# magnetorquer_board.net
KiCad netlist of a schematic drawn in EAGLE
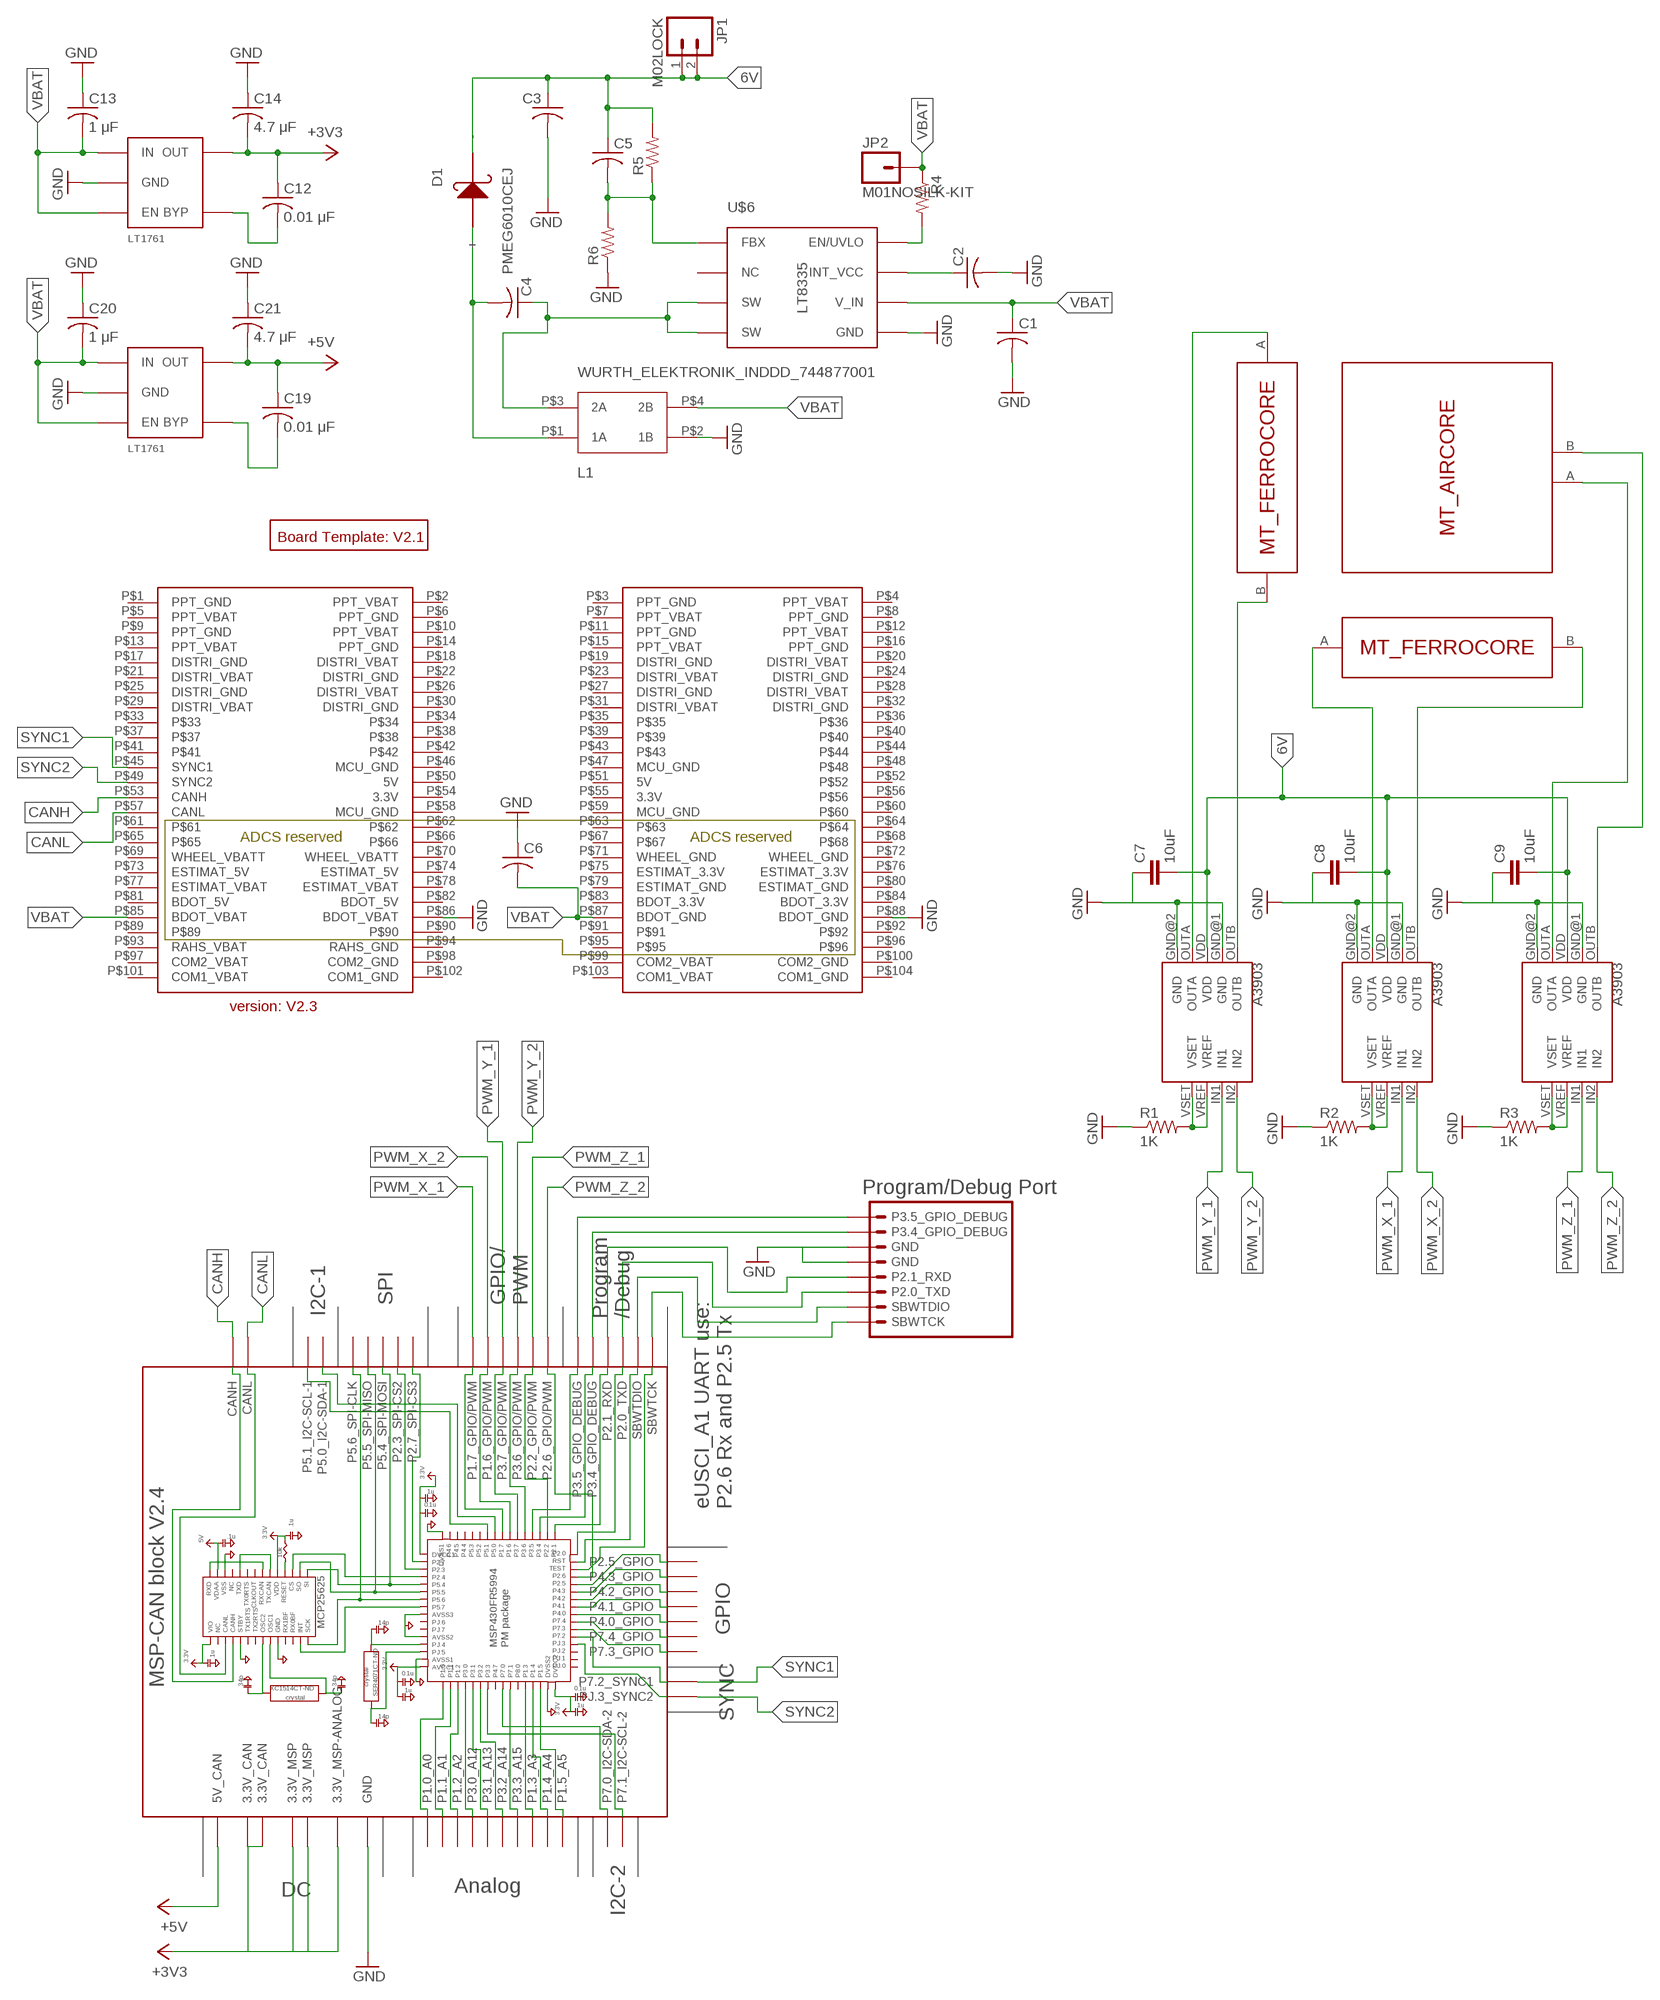
[diagram p0: schematic, sheet 1]

(export (version "E")
  (design (tool "Eeschema 10.0.6"))
  (components
    (comp (ref "C1")
      (value "C-USC0805")
      (footprint "eagle-import:C0805")
      (libsource (lib "eagle-import") (part "C-USC0805"))
    )
    (comp (ref "C2")
      (value "C-USC0805")
      (footprint "eagle-import:C0805")
      (libsource (lib "eagle-import") (part "C-USC0805"))
    )
    (comp (ref "C3")
      (value "C-USC0805")
      (footprint "eagle-import:C0805")
      (libsource (lib "eagle-import") (part "C-USC0805"))
    )
    (comp (ref "C4")
      (value "C-USC0805")
      (footprint "eagle-import:C0805")
      (libsource (lib "eagle-import") (part "C-USC0805"))
    )
    (comp (ref "C5")
      (value "C-USC0805")
      (footprint "eagle-import:C0805")
      (libsource (lib "eagle-import") (part "C-USC0805"))
    )
    (comp (ref "C6")
      (value "C-USC0805")
      (footprint "eagle-import:C0805")
      (libsource (lib "eagle-import") (part "C-USC0805"))
    )
    (comp (ref "C7")
      (value "10uF")
      (footprint "eagle-import:C0805")
      (libsource (lib "eagle-import") (part "C-EUC0805"))
    )
    (comp (ref "C8")
      (value "10uF")
      (footprint "eagle-import:C0805")
      (libsource (lib "eagle-import") (part "C-EUC0805"))
    )
    (comp (ref "C9")
      (value "10uF")
      (footprint "eagle-import:C0805")
      (libsource (lib "eagle-import") (part "C-EUC0805"))
    )
    (comp (ref "C12")
      (value "0.01 μF")
      (footprint "eagle-import:C0805")
      (libsource (lib "eagle-import") (part "C-USC0805"))
    )
    (comp (ref "C13")
      (value "1 μF")
      (footprint "eagle-import:C0805")
      (libsource (lib "eagle-import") (part "C-USC0805"))
    )
    (comp (ref "C14")
      (value "4.7 μF")
      (footprint "eagle-import:C0805")
      (libsource (lib "eagle-import") (part "C-USC0805"))
    )
    (comp (ref "C19")
      (value "0.01 μF")
      (footprint "eagle-import:C0805")
      (libsource (lib "eagle-import") (part "C-USC0805"))
    )
    (comp (ref "C20")
      (value "1 μF")
      (footprint "eagle-import:C0805")
      (libsource (lib "eagle-import") (part "C-USC0805"))
    )
    (comp (ref "C21")
      (value "4.7 μF")
      (footprint "eagle-import:C0805")
      (libsource (lib "eagle-import") (part "C-USC0805"))
    )
    (comp (ref "D1")
      (value "PMEG6010CEJ")
      (footprint "eagle-import:SC-90")
      (libsource (lib "eagle-import") (part "PMEG6010CEJ"))
    )
    (comp (ref "JP1")
      (value "M02LOCK")
      (footprint "eagle-import:1X02_LOCK")
      (libsource (lib "eagle-import") (part "M02LOCK"))
    )
    (comp (ref "JP2")
      (value "M01NOSILK-KIT")
      (footprint "eagle-import:1X01NS-KIT")
      (libsource (lib "eagle-import") (part "M01NOSILK-KIT"))
    )
    (comp (ref "L1")
      (value "WURTH_ELEKTRONIK_INDDD_744877001")
      (footprint "eagle-import:WURTH_ELEKTRONIK_INDDD_744877001")
      (libsource (lib "eagle-import") (part "WURTH_ELEKTRONIK_INDDD_744877001"))
    )
    (comp (ref "LDO_3V1")
      (value "LINEAR_LDO_LT1761-X")
      (footprint "eagle-import:SOT-23-5")
      (libsource (lib "eagle-import") (part "LINEAR_LDO_LT1761-X"))
    )
    (comp (ref "LDO_5V1")
      (value "LINEAR_LDO_LT1761-X")
      (footprint "eagle-import:SOT-23-5")
      (libsource (lib "eagle-import") (part "LINEAR_LDO_LT1761-X"))
    )
    (comp (ref "R1")
      (value "1K")
      (footprint "eagle-import:R0603")
      (libsource (lib "eagle-import") (part "R-US_R0603"))
    )
    (comp (ref "R2")
      (value "1K")
      (footprint "eagle-import:R0603")
      (libsource (lib "eagle-import") (part "R-US_R0603"))
    )
    (comp (ref "R3")
      (value "1K")
      (footprint "eagle-import:R0603")
      (libsource (lib "eagle-import") (part "R-US_R0603"))
    )
    (comp (ref "R4")
      (value "R-US_R0805")
      (footprint "eagle-import:R0805")
      (libsource (lib "eagle-import") (part "R-US_R0805"))
    )
    (comp (ref "R5")
      (value "R-US_R0805")
      (footprint "eagle-import:R0805")
      (libsource (lib "eagle-import") (part "R-US_R0805"))
    )
    (comp (ref "R6")
      (value "R-US_R0805")
      (footprint "eagle-import:R0805")
      (libsource (lib "eagle-import") (part "R-US_R0805"))
    )
    (comp (ref "U$1")
      (value "PC104_CONNECTOR")
      (footprint "eagle-import:PC104_CONNECTOR")
      (libsource (lib "eagle-import") (part "PC104_CONNECTOR"))
    )
    (comp (ref "U$2")
      (value "BOARD_TEMPLATE1")
      (footprint "eagle-import:BOARD_TEMPLATE")
      (libsource (lib "eagle-import") (part "BOARD_TEMPLATE1"))
    )
    (comp (ref "U$3")
      (value "MT_AIRCORE")
      (footprint "eagle-import:MT_AIRCORE")
      (libsource (lib "eagle-import") (part "MT_AIRCORE"))
    )
    (comp (ref "U$4")
      (value "MT_FERROCORE")
      (footprint "eagle-import:MT_FERROCORE")
      (libsource (lib "eagle-import") (part "MT_FERROCORE"))
    )
    (comp (ref "U$5")
      (value "MT_FERROCORE")
      (footprint "eagle-import:MT_FERROCORE")
      (libsource (lib "eagle-import") (part "MT_FERROCORE"))
    )
    (comp (ref "U$6")
      (value "LT8335")
      (footprint "eagle-import:DDB")
      (libsource (lib "eagle-import") (part "LT8335"))
    )
    (comp (ref "U$7")
      (value "MSP-CAN_BLOCK")
      (footprint "eagle-import:MSP-CAN_BLOCK")
      (libsource (lib "eagle-import") (part "MSP-CAN_BLOCK"))
    )
    (comp (ref "U$8")
      (value "PROGRAM/DEBUG_PORT")
      (footprint "eagle-import:1X08_CONNECTOR")
      (libsource (lib "eagle-import") (part "PROGRAM/DEBUG_PORT"))
    )
    (comp (ref "U1")
      (value "A3903")
      (footprint "eagle-import:DFN-8EE")
      (libsource (lib "eagle-import") (part "A3903"))
    )
    (comp (ref "U2")
      (value "A3903")
      (footprint "eagle-import:DFN-8EE")
      (libsource (lib "eagle-import") (part "A3903"))
    )
    (comp (ref "U3")
      (value "A3903")
      (footprint "eagle-import:DFN-8EE")
      (libsource (lib "eagle-import") (part "A3903"))
    )
  )
  (nets
    (net (code "1") (name "+3V3") (class "Default")
      (node (ref "C12") (pin "1") (pinfunction "1_1") (pintype "passive"))
      (node (ref "C14") (pin "2") (pinfunction "2_2") (pintype "passive"))
      (node (ref "LDO_3V1") (pin "P$5") (pinfunction "OUT_P$5") (pintype "bidirectional"))
      (node (ref "U$7") (pin "3.3V@CAN1") (pinfunction "3.3V_CAN_3.3V@CAN1") (pintype "bidirectional"))
      (node (ref "U$7") (pin "3.3V@CAN2") (pinfunction "3.3V_CAN_3.3V@CAN2") (pintype "bidirectional"))
      (node (ref "U$7") (pin "3.3V@MSP1") (pinfunction "3.3V_MSP_3.3V@MSP1") (pintype "bidirectional"))
      (node (ref "U$7") (pin "3.3V@MSP2") (pinfunction "3.3V_MSP_3.3V@MSP2") (pintype "bidirectional"))
      (node (ref "U$7") (pin "3.3V_ANALOG@MSP2") (pinfunction "3.3V_MSP-ANALOG_3.3V_ANALOG@MSP2") (pintype "bidirectional"))
    )
    (net (code "2") (name "+5V") (class "Default")
      (node (ref "C19") (pin "1") (pinfunction "1_1") (pintype "passive"))
      (node (ref "C21") (pin "2") (pinfunction "2_2") (pintype "passive"))
      (node (ref "LDO_5V1") (pin "P$5") (pinfunction "OUT_P$5") (pintype "bidirectional"))
      (node (ref "U$7") (pin "5V") (pinfunction "5V_CAN_5V") (pintype "bidirectional"))
    )
    (net (code "3") (name "6V") (class "Default")
      (node (ref "C3") (pin "1") (pinfunction "1_1") (pintype "passive"))
      (node (ref "C5") (pin "1") (pinfunction "1_1") (pintype "passive"))
      (node (ref "C7") (pin "2") (pinfunction "2_2") (pintype "passive"))
      (node (ref "C8") (pin "2") (pinfunction "2_2") (pintype "passive"))
      (node (ref "C9") (pin "2") (pinfunction "2_2") (pintype "passive"))
      (node (ref "D1") (pin "P$2") (pinfunction "-_P$2") (pintype "bidirectional"))
      (node (ref "JP1") (pin "1") (pinfunction "1_1") (pintype "passive"))
      (node (ref "JP1") (pin "2") (pinfunction "2_2") (pintype "passive"))
      (node (ref "R5") (pin "2") (pinfunction "2_2") (pintype "passive"))
      (node (ref "U1") (pin "VDD") (pinfunction "VDD_VDD") (pintype "power_in"))
      (node (ref "U2") (pin "VDD") (pinfunction "VDD_VDD") (pintype "power_in"))
      (node (ref "U3") (pin "VDD") (pinfunction "VDD_VDD") (pintype "power_in"))
    )
    (net (code "4") (name "CANH") (class "Default")
      (node (ref "U$1") (pin "P$53") (pinfunction "CANH_P$53") (pintype "bidirectional"))
      (node (ref "U$7") (pin "CANH") (pinfunction "CANH_CANH") (pintype "bidirectional"))
    )
    (net (code "5") (name "CANL") (class "Default")
      (node (ref "U$1") (pin "P$57") (pinfunction "CANL_P$57") (pintype "bidirectional"))
      (node (ref "U$7") (pin "CANL") (pinfunction "CANL_CANL") (pintype "bidirectional"))
    )
    (net (code "6") (name "GND") (class "Default")
      (node (ref "C1") (pin "2") (pinfunction "2_2") (pintype "passive"))
      (node (ref "C13") (pin "1") (pinfunction "1_1") (pintype "passive"))
      (node (ref "C14") (pin "1") (pinfunction "1_1") (pintype "passive"))
      (node (ref "C2") (pin "2") (pinfunction "2_2") (pintype "passive"))
      (node (ref "C20") (pin "1") (pinfunction "1_1") (pintype "passive"))
      (node (ref "C21") (pin "1") (pinfunction "1_1") (pintype "passive"))
      (node (ref "C3") (pin "2") (pinfunction "2_2") (pintype "passive"))
      (node (ref "C6") (pin "1") (pinfunction "1_1") (pintype "passive"))
      (node (ref "C7") (pin "1") (pinfunction "1_1") (pintype "passive"))
      (node (ref "C8") (pin "1") (pinfunction "1_1") (pintype "passive"))
      (node (ref "C9") (pin "1") (pinfunction "1_1") (pintype "passive"))
      (node (ref "L1") (pin "P$2") (pinfunction "1B_P$2") (pintype "bidirectional"))
      (node (ref "LDO_3V1") (pin "P$2") (pinfunction "GND_P$2") (pintype "bidirectional"))
      (node (ref "LDO_5V1") (pin "P$2") (pinfunction "GND_P$2") (pintype "bidirectional"))
      (node (ref "R1") (pin "1") (pinfunction "1_1") (pintype "passive"))
      (node (ref "R2") (pin "1") (pinfunction "1_1") (pintype "passive"))
      (node (ref "R3") (pin "1") (pinfunction "1_1") (pintype "passive"))
      (node (ref "R6") (pin "1") (pinfunction "1_1") (pintype "passive"))
      (node (ref "U$1") (pin "P$86") (pinfunction "BDOT_VBAT_P$86") (pintype "bidirectional"))
      (node (ref "U$1") (pin "P$88") (pinfunction "BDOT_GND_P$88") (pintype "bidirectional"))
      (node (ref "U$6") (pin "GND") (pinfunction "GND_GND") (pintype "bidirectional"))
      (node (ref "U$6") (pin "P$5") (pinfunction "GND_P$5") (pintype "bidirectional"))
      (node (ref "U$7") (pin "GND@1") (pinfunction "GND_GND@1") (pintype "bidirectional"))
      (node (ref "U$7") (pin "GND@10") (pinfunction "GND_GND@10") (pintype "bidirectional"))
      (node (ref "U$7") (pin "GND@11") (pinfunction "GND_GND@11") (pintype "bidirectional"))
      (node (ref "U$7") (pin "GND@12") (pinfunction "GND_GND@12") (pintype "bidirectional"))
      (node (ref "U$7") (pin "GND@13") (pinfunction "GND_GND@13") (pintype "bidirectional"))
      (node (ref "U$7") (pin "GND@14") (pinfunction "GND_GND@14") (pintype "bidirectional"))
      (node (ref "U$7") (pin "GND@15") (pinfunction "GND_GND@15") (pintype "bidirectional"))
      (node (ref "U$7") (pin "GND@16") (pinfunction "GND_GND@16") (pintype "bidirectional"))
      (node (ref "U$7") (pin "GND@17") (pinfunction "GND_GND@17") (pintype "bidirectional"))
      (node (ref "U$7") (pin "GND@2") (pinfunction "GND_GND@2") (pintype "bidirectional"))
      (node (ref "U$7") (pin "GND@26") (pinfunction "GND_GND@26") (pintype "bidirectional"))
      (node (ref "U$7") (pin "GND@3") (pinfunction "GND_GND@3") (pintype "bidirectional"))
      (node (ref "U$7") (pin "GND@4") (pinfunction "GND_GND@4") (pintype "bidirectional"))
      (node (ref "U$7") (pin "GND@5") (pinfunction "GND_GND@5") (pintype "bidirectional"))
      (node (ref "U$7") (pin "GND@7") (pinfunction "GND_GND@7") (pintype "bidirectional"))
      (node (ref "U$7") (pin "GND@8") (pinfunction "GND_GND@8") (pintype "bidirectional"))
      (node (ref "U$7") (pin "GND@9") (pinfunction "GND_GND@9") (pintype "bidirectional"))
      (node (ref "U$8") (pin "5") (pinfunction "GND_5") (pintype "bidirectional"))
      (node (ref "U$8") (pin "6") (pinfunction "GND_6") (pintype "bidirectional"))
      (node (ref "U1") (pin "GND@1") (pinfunction "GND_GND@1") (pintype "power_in"))
      (node (ref "U1") (pin "GND@2") (pinfunction "GND_GND@2") (pintype "power_in"))
      (node (ref "U2") (pin "GND@1") (pinfunction "GND_GND@1") (pintype "power_in"))
      (node (ref "U2") (pin "GND@2") (pinfunction "GND_GND@2") (pintype "power_in"))
      (node (ref "U3") (pin "GND@1") (pinfunction "GND_GND@1") (pintype "power_in"))
      (node (ref "U3") (pin "GND@2") (pinfunction "GND_GND@2") (pintype "power_in"))
    )
    (net (code "7") (name "Net-(D1-+)") (class "Default")
      (node (ref "C4") (pin "2") (pinfunction "2_2") (pintype "passive"))
      (node (ref "D1") (pin "P$1") (pinfunction "+_P$1") (pintype "bidirectional"))
      (node (ref "L1") (pin "P$1") (pinfunction "1A_P$1") (pintype "bidirectional"))
    )
    (net (code "8") (name "Net-(L1-2A)") (class "Default")
      (node (ref "C4") (pin "1") (pinfunction "1_1") (pintype "passive"))
      (node (ref "L1") (pin "P$3") (pinfunction "2A_P$3") (pintype "bidirectional"))
      (node (ref "U$6") (pin "P$3") (pinfunction "SW_P$3") (pintype "bidirectional"))
      (node (ref "U$6") (pin "P$4") (pinfunction "SW_P$4") (pintype "bidirectional"))
    )
    (net (code "9") (name "Net-(LDO_3V1-BYP)") (class "Default")
      (node (ref "C12") (pin "2") (pinfunction "2_2") (pintype "passive"))
      (node (ref "LDO_3V1") (pin "P$4") (pinfunction "BYP_P$4") (pintype "bidirectional"))
    )
    (net (code "10") (name "Net-(LDO_5V1-BYP)") (class "Default")
      (node (ref "C19") (pin "2") (pinfunction "2_2") (pintype "passive"))
      (node (ref "LDO_5V1") (pin "P$4") (pinfunction "BYP_P$4") (pintype "bidirectional"))
    )
    (net (code "11") (name "Net-(R1-Pad2)") (class "Default")
      (node (ref "R1") (pin "2") (pinfunction "2_2") (pintype "passive"))
      (node (ref "U1") (pin "VREF") (pinfunction "VREF_VREF") (pintype "power_in"))
      (node (ref "U1") (pin "VSET") (pinfunction "VSET_VSET") (pintype "bidirectional"))
    )
    (net (code "12") (name "Net-(R2-Pad2)") (class "Default")
      (node (ref "R2") (pin "2") (pinfunction "2_2") (pintype "passive"))
      (node (ref "U2") (pin "VREF") (pinfunction "VREF_VREF") (pintype "power_in"))
      (node (ref "U2") (pin "VSET") (pinfunction "VSET_VSET") (pintype "bidirectional"))
    )
    (net (code "13") (name "Net-(R3-Pad2)") (class "Default")
      (node (ref "R3") (pin "2") (pinfunction "2_2") (pintype "passive"))
      (node (ref "U3") (pin "VREF") (pinfunction "VREF_VREF") (pintype "power_in"))
      (node (ref "U3") (pin "VSET") (pinfunction "VSET_VSET") (pintype "bidirectional"))
    )
    (net (code "14") (name "Net-(U$3-PadA)") (class "Default")
      (node (ref "U$3") (pin "A") (pinfunction "A_A") (pintype "bidirectional"))
      (node (ref "U3") (pin "OUTA") (pinfunction "OUTA_OUTA") (pintype "output"))
    )
    (net (code "15") (name "Net-(U$3-PadB)") (class "Default")
      (node (ref "U$3") (pin "B") (pinfunction "B_B") (pintype "bidirectional"))
      (node (ref "U3") (pin "OUTB") (pinfunction "OUTB_OUTB") (pintype "output"))
    )
    (net (code "16") (name "Net-(U$4-PadA)") (class "Default")
      (node (ref "U$4") (pin "A") (pinfunction "A_A") (pintype "bidirectional"))
      (node (ref "U1") (pin "OUTA") (pinfunction "OUTA_OUTA") (pintype "output"))
    )
    (net (code "17") (name "Net-(U$4-PadB)") (class "Default")
      (node (ref "U$4") (pin "B") (pinfunction "B_B") (pintype "bidirectional"))
      (node (ref "U1") (pin "OUTB") (pinfunction "OUTB_OUTB") (pintype "output"))
    )
    (net (code "18") (name "Net-(U$5-PadA)") (class "Default")
      (node (ref "U$5") (pin "A") (pinfunction "A_A") (pintype "bidirectional"))
      (node (ref "U2") (pin "OUTA") (pinfunction "OUTA_OUTA") (pintype "output"))
    )
    (net (code "19") (name "Net-(U$5-PadB)") (class "Default")
      (node (ref "U$5") (pin "B") (pinfunction "B_B") (pintype "bidirectional"))
      (node (ref "U2") (pin "OUTB") (pinfunction "OUTB_OUTB") (pintype "output"))
    )
    (net (code "20") (name "Net-(U$6-EN{slash}UVLO)") (class "Default")
      (node (ref "R4") (pin "2") (pinfunction "2_2") (pintype "passive"))
      (node (ref "U$6") (pin "P$8") (pinfunction "EN/UVLO_P$8") (pintype "bidirectional"))
    )
    (net (code "21") (name "Net-(U$6-FBX)") (class "Default")
      (node (ref "C5") (pin "2") (pinfunction "2_2") (pintype "passive"))
      (node (ref "R5") (pin "1") (pinfunction "1_1") (pintype "passive"))
      (node (ref "R6") (pin "2") (pinfunction "2_2") (pintype "passive"))
      (node (ref "U$6") (pin "P$1") (pinfunction "FBX_P$1") (pintype "bidirectional"))
    )
    (net (code "22") (name "Net-(U$6-INT_VCC)") (class "Default")
      (node (ref "C2") (pin "1") (pinfunction "1_1") (pintype "passive"))
      (node (ref "U$6") (pin "P$7") (pinfunction "INT_VCC_P$7") (pintype "bidirectional"))
    )
    (net (code "23") (name "Net-(U$7-PadSBWTCK)") (class "Default")
      (node (ref "U$7") (pin "SBWTCK") (pinfunction "SBWTCK_SBWTCK") (pintype "bidirectional"))
      (node (ref "U$8") (pin "SBWTCK") (pinfunction "SBWTCK_SBWTCK") (pintype "bidirectional"))
    )
    (net (code "24") (name "Net-(U$8-P2.0_TXD)") (class "Default")
      (node (ref "U$7") (pin "P2.0_TXD") (pinfunction "P2.0_TXD_P2.0_TXD") (pintype "bidirectional"))
      (node (ref "U$8") (pin "3") (pinfunction "P2.0_TXD_3") (pintype "bidirectional"))
    )
    (net (code "25") (name "Net-(U$8-P2.1_RXD)") (class "Default")
      (node (ref "U$7") (pin "P2.1_RXD") (pinfunction "P2.1_RXD_P2.1_RXD") (pintype "bidirectional"))
      (node (ref "U$8") (pin "4") (pinfunction "P2.1_RXD_4") (pintype "bidirectional"))
    )
    (net (code "26") (name "Net-(U$8-P3.4_GPIO_DEBUG)") (class "Default")
      (node (ref "U$7") (pin "P3.4_GPIO_DEBUG") (pinfunction "P3.4_GPIO_DEBUG_P3.4_GPIO_DEBUG") (pintype "bidirectional"))
      (node (ref "U$8") (pin "7") (pinfunction "P3.4_GPIO_DEBUG_7") (pintype "bidirectional"))
    )
    (net (code "27") (name "Net-(U$8-P3.5_GPIO_DEBUG)") (class "Default")
      (node (ref "U$7") (pin "P3.5_GPIO_DEBUG") (pinfunction "P3.5_GPIO_DEBUG_P3.5_GPIO_DEBUG") (pintype "bidirectional"))
      (node (ref "U$8") (pin "8") (pinfunction "P3.5_GPIO_DEBUG_8") (pintype "bidirectional"))
    )
    (net (code "28") (name "Net-(U$8-SBWTDIO)") (class "Default")
      (node (ref "U$7") (pin "SBWTDIO") (pinfunction "SBWTDIO_SBWTDIO") (pintype "bidirectional"))
      (node (ref "U$8") (pin "2") (pinfunction "SBWTDIO_2") (pintype "bidirectional"))
    )
    (net (code "29") (name "PWM_X_1") (class "Default")
      (node (ref "U$7") (pin "P1.7_GPIO/PWM") (pinfunction "P1.7_GPIO/PWM_P1.7_GPIO/PWM") (pintype "bidirectional"))
      (node (ref "U2") (pin "IN1") (pinfunction "IN1_IN1") (pintype "input"))
    )
    (net (code "30") (name "PWM_X_2") (class "Default")
      (node (ref "U$7") (pin "P1.6_GPIO/PWM") (pinfunction "P1.6_GPIO/PWM_P1.6_GPIO/PWM") (pintype "bidirectional"))
      (node (ref "U2") (pin "IN2") (pinfunction "IN2_IN2") (pintype "input"))
    )
    (net (code "31") (name "PWM_Y_1") (class "Default")
      (node (ref "U$7") (pin "P3.7_GPIO/PWM") (pinfunction "P3.7_GPIO/PWM_P3.7_GPIO/PWM") (pintype "bidirectional"))
      (node (ref "U1") (pin "IN1") (pinfunction "IN1_IN1") (pintype "input"))
    )
    (net (code "32") (name "PWM_Y_2") (class "Default")
      (node (ref "U$7") (pin "P3.6_GPIO/PWM") (pinfunction "P3.6_GPIO/PWM_P3.6_GPIO/PWM") (pintype "bidirectional"))
      (node (ref "U1") (pin "IN2") (pinfunction "IN2_IN2") (pintype "input"))
    )
    (net (code "33") (name "PWM_Z_1") (class "Default")
      (node (ref "U$7") (pin "P2.2_GPIO/PWM") (pinfunction "P2.2_GPIO/PWM_P2.2_GPIO/PWM") (pintype "bidirectional"))
      (node (ref "U3") (pin "IN1") (pinfunction "IN1_IN1") (pintype "input"))
    )
    (net (code "34") (name "PWM_Z_2") (class "Default")
      (node (ref "U$7") (pin "P2.6_GPIO/PWM") (pinfunction "P2.6_GPIO/PWM_P2.6_GPIO/PWM") (pintype "bidirectional"))
      (node (ref "U3") (pin "IN2") (pinfunction "IN2_IN2") (pintype "input"))
    )
    (net (code "35") (name "SYNC1") (class "Default")
      (node (ref "U$1") (pin "P$45") (pinfunction "SYNC1_P$45") (pintype "bidirectional"))
      (node (ref "U$7") (pin "P7.2_SYNC1") (pinfunction "P7.2_SYNC1_P7.2_SYNC1") (pintype "bidirectional"))
    )
    (net (code "36") (name "SYNC2") (class "Default")
      (node (ref "U$1") (pin "P$49") (pinfunction "SYNC2_P$49") (pintype "bidirectional"))
      (node (ref "U$7") (pin "PJ.3_SYNC2") (pinfunction "PJ.3_SYNC2_PJ.3_SYNC2") (pintype "bidirectional"))
    )
    (net (code "37") (name "VBAT") (class "Default")
      (node (ref "C1") (pin "1") (pinfunction "1_1") (pintype "passive"))
      (node (ref "C13") (pin "2") (pinfunction "2_2") (pintype "passive"))
      (node (ref "C20") (pin "2") (pinfunction "2_2") (pintype "passive"))
      (node (ref "C6") (pin "2") (pinfunction "2_2") (pintype "passive"))
      (node (ref "JP2") (pin "1") (pinfunction "1_1") (pintype "passive"))
      (node (ref "L1") (pin "P$4") (pinfunction "2B_P$4") (pintype "bidirectional"))
      (node (ref "LDO_3V1") (pin "P$1") (pinfunction "IN_P$1") (pintype "bidirectional"))
      (node (ref "LDO_3V1") (pin "P$3") (pinfunction "EN_P$3") (pintype "bidirectional"))
      (node (ref "LDO_5V1") (pin "P$1") (pinfunction "IN_P$1") (pintype "bidirectional"))
      (node (ref "LDO_5V1") (pin "P$3") (pinfunction "EN_P$3") (pintype "bidirectional"))
      (node (ref "R4") (pin "1") (pinfunction "1_1") (pintype "passive"))
      (node (ref "U$1") (pin "P$85") (pinfunction "BDOT_VBAT_P$85") (pintype "bidirectional"))
      (node (ref "U$1") (pin "P$87") (pinfunction "BDOT_GND_P$87") (pintype "bidirectional"))
      (node (ref "U$6") (pin "P$6") (pinfunction "V_IN_P$6") (pintype "bidirectional"))
    )
    (net (code "38") (name "unconnected-(U$1-3.3V-PadP$54)") (class "Default")
      (node (ref "U$1") (pin "P$54") (pinfunction "3.3V_P$54") (pintype "bidirectional"))
    )
    (net (code "39") (name "unconnected-(U$1-3.3V-PadP$55)") (class "Default")
      (node (ref "U$1") (pin "P$55") (pinfunction "3.3V_P$55") (pintype "bidirectional"))
    )
    (net (code "40") (name "unconnected-(U$1-5V-PadP$50)") (class "Default")
      (node (ref "U$1") (pin "P$50") (pinfunction "5V_P$50") (pintype "bidirectional"))
    )
    (net (code "41") (name "unconnected-(U$1-5V-PadP$51)") (class "Default")
      (node (ref "U$1") (pin "P$51") (pinfunction "5V_P$51") (pintype "bidirectional"))
    )
    (net (code "42") (name "unconnected-(U$1-BDOT_3.3V-PadP$83)") (class "Default")
      (node (ref "U$1") (pin "P$83") (pinfunction "BDOT_3.3V_P$83") (pintype "bidirectional"))
    )
    (net (code "43") (name "unconnected-(U$1-BDOT_3.3V-PadP$84)") (class "Default")
      (node (ref "U$1") (pin "P$84") (pinfunction "BDOT_3.3V_P$84") (pintype "bidirectional"))
    )
    (net (code "44") (name "unconnected-(U$1-BDOT_5V-PadP$81)") (class "Default")
      (node (ref "U$1") (pin "P$81") (pinfunction "BDOT_5V_P$81") (pintype "bidirectional"))
    )
    (net (code "45") (name "unconnected-(U$1-BDOT_5V-PadP$82)") (class "Default")
      (node (ref "U$1") (pin "P$82") (pinfunction "BDOT_5V_P$82") (pintype "bidirectional"))
    )
    (net (code "46") (name "unconnected-(U$1-COM1_GND-PadP$102)") (class "Default")
      (node (ref "U$1") (pin "P$102") (pinfunction "COM1_GND_P$102") (pintype "bidirectional"))
    )
    (net (code "47") (name "unconnected-(U$1-COM1_GND-PadP$104)") (class "Default")
      (node (ref "U$1") (pin "P$104") (pinfunction "COM1_GND_P$104") (pintype "bidirectional"))
    )
    (net (code "48") (name "unconnected-(U$1-COM1_VBAT-PadP$101)") (class "Default")
      (node (ref "U$1") (pin "P$101") (pinfunction "COM1_VBAT_P$101") (pintype "bidirectional"))
    )
    (net (code "49") (name "unconnected-(U$1-COM1_VBAT-PadP$103)") (class "Default")
      (node (ref "U$1") (pin "P$103") (pinfunction "COM1_VBAT_P$103") (pintype "bidirectional"))
    )
    (net (code "50") (name "unconnected-(U$1-COM2_GND-PadP$98)") (class "Default")
      (node (ref "U$1") (pin "P$98") (pinfunction "COM2_GND_P$98") (pintype "bidirectional"))
    )
    (net (code "51") (name "unconnected-(U$1-COM2_GND-PadP$100)") (class "Default")
      (node (ref "U$1") (pin "P$100") (pinfunction "COM2_GND_P$100") (pintype "bidirectional"))
    )
    (net (code "52") (name "unconnected-(U$1-COM2_VBAT-PadP$97)") (class "Default")
      (node (ref "U$1") (pin "P$97") (pinfunction "COM2_VBAT_P$97") (pintype "bidirectional"))
    )
    (net (code "53") (name "unconnected-(U$1-COM2_VBAT-PadP$99)") (class "Default")
      (node (ref "U$1") (pin "P$99") (pinfunction "COM2_VBAT_P$99") (pintype "bidirectional"))
    )
    (net (code "54") (name "unconnected-(U$1-DISTRI_GND-PadP$17)") (class "Default")
      (node (ref "U$1") (pin "P$17") (pinfunction "DISTRI_GND_P$17") (pintype "bidirectional"))
    )
    (net (code "55") (name "unconnected-(U$1-DISTRI_GND-PadP$19)") (class "Default")
      (node (ref "U$1") (pin "P$19") (pinfunction "DISTRI_GND_P$19") (pintype "bidirectional"))
    )
    (net (code "56") (name "unconnected-(U$1-DISTRI_GND-PadP$22)") (class "Default")
      (node (ref "U$1") (pin "P$22") (pinfunction "DISTRI_GND_P$22") (pintype "bidirectional"))
    )
    (net (code "57") (name "unconnected-(U$1-DISTRI_GND-PadP$24)") (class "Default")
      (node (ref "U$1") (pin "P$24") (pinfunction "DISTRI_GND_P$24") (pintype "bidirectional"))
    )
    (net (code "58") (name "unconnected-(U$1-DISTRI_GND-PadP$25)") (class "Default")
      (node (ref "U$1") (pin "P$25") (pinfunction "DISTRI_GND_P$25") (pintype "bidirectional"))
    )
    (net (code "59") (name "unconnected-(U$1-DISTRI_GND-PadP$27)") (class "Default")
      (node (ref "U$1") (pin "P$27") (pinfunction "DISTRI_GND_P$27") (pintype "bidirectional"))
    )
    (net (code "60") (name "unconnected-(U$1-DISTRI_GND-PadP$30)") (class "Default")
      (node (ref "U$1") (pin "P$30") (pinfunction "DISTRI_GND_P$30") (pintype "bidirectional"))
    )
    (net (code "61") (name "unconnected-(U$1-DISTRI_GND-PadP$32)") (class "Default")
      (node (ref "U$1") (pin "P$32") (pinfunction "DISTRI_GND_P$32") (pintype "bidirectional"))
    )
    (net (code "62") (name "unconnected-(U$1-DISTRI_VBAT-PadP$18)") (class "Default")
      (node (ref "U$1") (pin "P$18") (pinfunction "DISTRI_VBAT_P$18") (pintype "bidirectional"))
    )
    (net (code "63") (name "unconnected-(U$1-DISTRI_VBAT-PadP$20)") (class "Default")
      (node (ref "U$1") (pin "P$20") (pinfunction "DISTRI_VBAT_P$20") (pintype "bidirectional"))
    )
    (net (code "64") (name "unconnected-(U$1-DISTRI_VBAT-PadP$21)") (class "Default")
      (node (ref "U$1") (pin "P$21") (pinfunction "DISTRI_VBAT_P$21") (pintype "bidirectional"))
    )
    (net (code "65") (name "unconnected-(U$1-DISTRI_VBAT-PadP$23)") (class "Default")
      (node (ref "U$1") (pin "P$23") (pinfunction "DISTRI_VBAT_P$23") (pintype "bidirectional"))
    )
    (net (code "66") (name "unconnected-(U$1-DISTRI_VBAT-PadP$26)") (class "Default")
      (node (ref "U$1") (pin "P$26") (pinfunction "DISTRI_VBAT_P$26") (pintype "bidirectional"))
    )
    (net (code "67") (name "unconnected-(U$1-DISTRI_VBAT-PadP$28)") (class "Default")
      (node (ref "U$1") (pin "P$28") (pinfunction "DISTRI_VBAT_P$28") (pintype "bidirectional"))
    )
    (net (code "68") (name "unconnected-(U$1-DISTRI_VBAT-PadP$29)") (class "Default")
      (node (ref "U$1") (pin "P$29") (pinfunction "DISTRI_VBAT_P$29") (pintype "bidirectional"))
    )
    (net (code "69") (name "unconnected-(U$1-DISTRI_VBAT-PadP$31)") (class "Default")
      (node (ref "U$1") (pin "P$31") (pinfunction "DISTRI_VBAT_P$31") (pintype "bidirectional"))
    )
    (net (code "70") (name "unconnected-(U$1-ESTIMAT_3.3V-PadP$75)") (class "Default")
      (node (ref "U$1") (pin "P$75") (pinfunction "ESTIMAT_3.3V_P$75") (pintype "bidirectional"))
    )
    (net (code "71") (name "unconnected-(U$1-ESTIMAT_3.3V-PadP$76)") (class "Default")
      (node (ref "U$1") (pin "P$76") (pinfunction "ESTIMAT_3.3V_P$76") (pintype "bidirectional"))
    )
    (net (code "72") (name "unconnected-(U$1-ESTIMAT_5V-PadP$73)") (class "Default")
      (node (ref "U$1") (pin "P$73") (pinfunction "ESTIMAT_5V_P$73") (pintype "bidirectional"))
    )
    (net (code "73") (name "unconnected-(U$1-ESTIMAT_5V-PadP$74)") (class "Default")
      (node (ref "U$1") (pin "P$74") (pinfunction "ESTIMAT_5V_P$74") (pintype "bidirectional"))
    )
    (net (code "74") (name "unconnected-(U$1-ESTIMAT_GND-PadP$79)") (class "Default")
      (node (ref "U$1") (pin "P$79") (pinfunction "ESTIMAT_GND_P$79") (pintype "bidirectional"))
    )
    (net (code "75") (name "unconnected-(U$1-ESTIMAT_GND-PadP$80)") (class "Default")
      (node (ref "U$1") (pin "P$80") (pinfunction "ESTIMAT_GND_P$80") (pintype "bidirectional"))
    )
    (net (code "76") (name "unconnected-(U$1-ESTIMAT_VBAT-PadP$77)") (class "Default")
      (node (ref "U$1") (pin "P$77") (pinfunction "ESTIMAT_VBAT_P$77") (pintype "bidirectional"))
    )
    (net (code "77") (name "unconnected-(U$1-ESTIMAT_VBAT-PadP$78)") (class "Default")
      (node (ref "U$1") (pin "P$78") (pinfunction "ESTIMAT_VBAT_P$78") (pintype "bidirectional"))
    )
    (net (code "78") (name "unconnected-(U$1-MCU_GND-PadP$46)") (class "Default")
      (node (ref "U$1") (pin "P$46") (pinfunction "MCU_GND_P$46") (pintype "bidirectional"))
    )
    (net (code "79") (name "unconnected-(U$1-MCU_GND-PadP$47)") (class "Default")
      (node (ref "U$1") (pin "P$47") (pinfunction "MCU_GND_P$47") (pintype "bidirectional"))
    )
    (net (code "80") (name "unconnected-(U$1-MCU_GND-PadP$58)") (class "Default")
      (node (ref "U$1") (pin "P$58") (pinfunction "MCU_GND_P$58") (pintype "bidirectional"))
    )
    (net (code "81") (name "unconnected-(U$1-MCU_GND-PadP$59)") (class "Default")
      (node (ref "U$1") (pin "P$59") (pinfunction "MCU_GND_P$59") (pintype "bidirectional"))
    )
    (net (code "82") (name "unconnected-(U$1-PPT_GND-PadP$1)") (class "Default")
      (node (ref "U$1") (pin "P$1") (pinfunction "PPT_GND_P$1") (pintype "bidirectional"))
    )
    (net (code "83") (name "unconnected-(U$1-PPT_GND-PadP$3)") (class "Default")
      (node (ref "U$1") (pin "P$3") (pinfunction "PPT_GND_P$3") (pintype "bidirectional"))
    )
    (net (code "84") (name "unconnected-(U$1-PPT_GND-PadP$6)") (class "Default")
      (node (ref "U$1") (pin "P$6") (pinfunction "PPT_GND_P$6") (pintype "bidirectional"))
    )
    (net (code "85") (name "unconnected-(U$1-PPT_GND-PadP$8)") (class "Default")
      (node (ref "U$1") (pin "P$8") (pinfunction "PPT_GND_P$8") (pintype "bidirectional"))
    )
    (net (code "86") (name "unconnected-(U$1-PPT_GND-PadP$9)") (class "Default")
      (node (ref "U$1") (pin "P$9") (pinfunction "PPT_GND_P$9") (pintype "bidirectional"))
    )
    (net (code "87") (name "unconnected-(U$1-PPT_GND-PadP$11)") (class "Default")
      (node (ref "U$1") (pin "P$11") (pinfunction "PPT_GND_P$11") (pintype "bidirectional"))
    )
    (net (code "88") (name "unconnected-(U$1-PPT_GND-PadP$14)") (class "Default")
      (node (ref "U$1") (pin "P$14") (pinfunction "PPT_GND_P$14") (pintype "bidirectional"))
    )
    (net (code "89") (name "unconnected-(U$1-PPT_GND-PadP$16)") (class "Default")
      (node (ref "U$1") (pin "P$16") (pinfunction "PPT_GND_P$16") (pintype "bidirectional"))
    )
    (net (code "90") (name "unconnected-(U$1-PPT_VBAT-PadP$2)") (class "Default")
      (node (ref "U$1") (pin "P$2") (pinfunction "PPT_VBAT_P$2") (pintype "bidirectional"))
    )
    (net (code "91") (name "unconnected-(U$1-PPT_VBAT-PadP$4)") (class "Default")
      (node (ref "U$1") (pin "P$4") (pinfunction "PPT_VBAT_P$4") (pintype "bidirectional"))
    )
    (net (code "92") (name "unconnected-(U$1-PPT_VBAT-PadP$5)") (class "Default")
      (node (ref "U$1") (pin "P$5") (pinfunction "PPT_VBAT_P$5") (pintype "bidirectional"))
    )
    (net (code "93") (name "unconnected-(U$1-PPT_VBAT-PadP$7)") (class "Default")
      (node (ref "U$1") (pin "P$7") (pinfunction "PPT_VBAT_P$7") (pintype "bidirectional"))
    )
    (net (code "94") (name "unconnected-(U$1-PPT_VBAT-PadP$10)") (class "Default")
      (node (ref "U$1") (pin "P$10") (pinfunction "PPT_VBAT_P$10") (pintype "bidirectional"))
    )
    (net (code "95") (name "unconnected-(U$1-PPT_VBAT-PadP$12)") (class "Default")
      (node (ref "U$1") (pin "P$12") (pinfunction "PPT_VBAT_P$12") (pintype "bidirectional"))
    )
    (net (code "96") (name "unconnected-(U$1-PPT_VBAT-PadP$13)") (class "Default")
      (node (ref "U$1") (pin "P$13") (pinfunction "PPT_VBAT_P$13") (pintype "bidirectional"))
    )
    (net (code "97") (name "unconnected-(U$1-PPT_VBAT-PadP$15)") (class "Default")
      (node (ref "U$1") (pin "P$15") (pinfunction "PPT_VBAT_P$15") (pintype "bidirectional"))
    )
    (net (code "98") (name "unconnected-(U$1-PadP$33)") (class "Default")
      (node (ref "U$1") (pin "P$33") (pinfunction "P$33_P$33") (pintype "bidirectional"))
    )
    (net (code "99") (name "unconnected-(U$1-PadP$34)") (class "Default")
      (node (ref "U$1") (pin "P$34") (pinfunction "P$34_P$34") (pintype "bidirectional"))
    )
    (net (code "100") (name "unconnected-(U$1-PadP$35)") (class "Default")
      (node (ref "U$1") (pin "P$35") (pinfunction "P$35_P$35") (pintype "bidirectional"))
    )
    (net (code "101") (name "unconnected-(U$1-PadP$36)") (class "Default")
      (node (ref "U$1") (pin "P$36") (pinfunction "P$36_P$36") (pintype "bidirectional"))
    )
    (net (code "102") (name "unconnected-(U$1-PadP$37)") (class "Default")
      (node (ref "U$1") (pin "P$37") (pinfunction "P$37_P$37") (pintype "bidirectional"))
    )
    (net (code "103") (name "unconnected-(U$1-PadP$38)") (class "Default")
      (node (ref "U$1") (pin "P$38") (pinfunction "P$38_P$38") (pintype "bidirectional"))
    )
    (net (code "104") (name "unconnected-(U$1-PadP$39)") (class "Default")
      (node (ref "U$1") (pin "P$39") (pinfunction "P$39_P$39") (pintype "bidirectional"))
    )
    (net (code "105") (name "unconnected-(U$1-PadP$40)") (class "Default")
      (node (ref "U$1") (pin "P$40") (pinfunction "P$40_P$40") (pintype "bidirectional"))
    )
    (net (code "106") (name "unconnected-(U$1-PadP$41)") (class "Default")
      (node (ref "U$1") (pin "P$41") (pinfunction "P$41_P$41") (pintype "bidirectional"))
    )
    (net (code "107") (name "unconnected-(U$1-PadP$42)") (class "Default")
      (node (ref "U$1") (pin "P$42") (pinfunction "P$42_P$42") (pintype "bidirectional"))
    )
    (net (code "108") (name "unconnected-(U$1-PadP$43)") (class "Default")
      (node (ref "U$1") (pin "P$43") (pinfunction "P$43_P$43") (pintype "bidirectional"))
    )
    (net (code "109") (name "unconnected-(U$1-PadP$44)") (class "Default")
      (node (ref "U$1") (pin "P$44") (pinfunction "P$44_P$44") (pintype "bidirectional"))
    )
    (net (code "110") (name "unconnected-(U$1-PadP$48)") (class "Default")
      (node (ref "U$1") (pin "P$48") (pinfunction "P$48_P$48") (pintype "bidirectional"))
    )
    (net (code "111") (name "unconnected-(U$1-PadP$52)") (class "Default")
      (node (ref "U$1") (pin "P$52") (pinfunction "P$52_P$52") (pintype "bidirectional"))
    )
    (net (code "112") (name "unconnected-(U$1-PadP$56)") (class "Default")
      (node (ref "U$1") (pin "P$56") (pinfunction "P$56_P$56") (pintype "bidirectional"))
    )
    (net (code "113") (name "unconnected-(U$1-PadP$60)") (class "Default")
      (node (ref "U$1") (pin "P$60") (pinfunction "P$60_P$60") (pintype "bidirectional"))
    )
    (net (code "114") (name "unconnected-(U$1-PadP$61)") (class "Default")
      (node (ref "U$1") (pin "P$61") (pinfunction "P$61_P$61") (pintype "bidirectional"))
    )
    (net (code "115") (name "unconnected-(U$1-PadP$62)") (class "Default")
      (node (ref "U$1") (pin "P$62") (pinfunction "P$62_P$62") (pintype "bidirectional"))
    )
    (net (code "116") (name "unconnected-(U$1-PadP$63)") (class "Default")
      (node (ref "U$1") (pin "P$63") (pinfunction "P$63_P$63") (pintype "bidirectional"))
    )
    (net (code "117") (name "unconnected-(U$1-PadP$64)") (class "Default")
      (node (ref "U$1") (pin "P$64") (pinfunction "P$64_P$64") (pintype "bidirectional"))
    )
    (net (code "118") (name "unconnected-(U$1-PadP$65)") (class "Default")
      (node (ref "U$1") (pin "P$65") (pinfunction "P$65_P$65") (pintype "bidirectional"))
    )
    (net (code "119") (name "unconnected-(U$1-PadP$66)") (class "Default")
      (node (ref "U$1") (pin "P$66") (pinfunction "P$66_P$66") (pintype "bidirectional"))
    )
    (net (code "120") (name "unconnected-(U$1-PadP$67)") (class "Default")
      (node (ref "U$1") (pin "P$67") (pinfunction "P$67_P$67") (pintype "bidirectional"))
    )
    (net (code "121") (name "unconnected-(U$1-PadP$68)") (class "Default")
      (node (ref "U$1") (pin "P$68") (pinfunction "P$68_P$68") (pintype "bidirectional"))
    )
    (net (code "122") (name "unconnected-(U$1-PadP$89)") (class "Default")
      (node (ref "U$1") (pin "P$89") (pinfunction "P$89_P$89") (pintype "bidirectional"))
    )
    (net (code "123") (name "unconnected-(U$1-PadP$90)") (class "Default")
      (node (ref "U$1") (pin "P$90") (pinfunction "P$90_P$90") (pintype "bidirectional"))
    )
    (net (code "124") (name "unconnected-(U$1-PadP$91)") (class "Default")
      (node (ref "U$1") (pin "P$91") (pinfunction "P$91_P$91") (pintype "bidirectional"))
    )
    (net (code "125") (name "unconnected-(U$1-PadP$92)") (class "Default")
      (node (ref "U$1") (pin "P$92") (pinfunction "P$92_P$92") (pintype "bidirectional"))
    )
    (net (code "126") (name "unconnected-(U$1-PadP$95)") (class "Default")
      (node (ref "U$1") (pin "P$95") (pinfunction "P$95_P$95") (pintype "bidirectional"))
    )
    (net (code "127") (name "unconnected-(U$1-PadP$96)") (class "Default")
      (node (ref "U$1") (pin "P$96") (pinfunction "P$96_P$96") (pintype "bidirectional"))
    )
    (net (code "128") (name "unconnected-(U$1-RAHS_GND-PadP$94)") (class "Default")
      (node (ref "U$1") (pin "P$94") (pinfunction "RAHS_GND_P$94") (pintype "bidirectional"))
    )
    (net (code "129") (name "unconnected-(U$1-RAHS_VBAT-PadP$93)") (class "Default")
      (node (ref "U$1") (pin "P$93") (pinfunction "RAHS_VBAT_P$93") (pintype "bidirectional"))
    )
    (net (code "130") (name "unconnected-(U$1-WHEEL_GND-PadP$71)") (class "Default")
      (node (ref "U$1") (pin "P$71") (pinfunction "WHEEL_GND_P$71") (pintype "bidirectional"))
    )
    (net (code "131") (name "unconnected-(U$1-WHEEL_GND-PadP$72)") (class "Default")
      (node (ref "U$1") (pin "P$72") (pinfunction "WHEEL_GND_P$72") (pintype "bidirectional"))
    )
    (net (code "132") (name "unconnected-(U$1-WHEEL_VBATT-PadP$69)") (class "Default")
      (node (ref "U$1") (pin "P$69") (pinfunction "WHEEL_VBATT_P$69") (pintype "bidirectional"))
    )
    (net (code "133") (name "unconnected-(U$1-WHEEL_VBATT-PadP$70)") (class "Default")
      (node (ref "U$1") (pin "P$70") (pinfunction "WHEEL_VBATT_P$70") (pintype "bidirectional"))
    )
    (net (code "134") (name "unconnected-(U$6-NC-PadP$2)") (class "Default")
      (node (ref "U$6") (pin "P$2") (pinfunction "NC_P$2") (pintype "bidirectional"))
    )
    (net (code "135") (name "unconnected-(U$7-P2.3_SPI-CS2-PadP2.4_SPI-CS2)") (class "Default")
      (node (ref "U$7") (pin "P2.4_SPI-CS2") (pinfunction "P2.3_SPI-CS2_P2.4_SPI-CS2") (pintype "bidirectional"))
    )
    (net (code "136") (name "unconnected-(U$7-PadP1.0_A0)") (class "Default")
      (node (ref "U$7") (pin "P1.0_A0") (pinfunction "P1.0_A0_P1.0_A0") (pintype "bidirectional"))
    )
    (net (code "137") (name "unconnected-(U$7-PadP1.1_A1)") (class "Default")
      (node (ref "U$7") (pin "P1.1_A1") (pinfunction "P1.1_A1_P1.1_A1") (pintype "bidirectional"))
    )
    (net (code "138") (name "unconnected-(U$7-PadP1.2_A2)") (class "Default")
      (node (ref "U$7") (pin "P1.2_A2") (pinfunction "P1.2_A2_P1.2_A2") (pintype "bidirectional"))
    )
    (net (code "139") (name "unconnected-(U$7-PadP1.3_A3)") (class "Default")
      (node (ref "U$7") (pin "P1.3_A3") (pinfunction "P1.3_A3_P1.3_A3") (pintype "bidirectional"))
    )
    (net (code "140") (name "unconnected-(U$7-PadP1.4_A4)") (class "Default")
      (node (ref "U$7") (pin "P1.4_A4") (pinfunction "P1.4_A4_P1.4_A4") (pintype "bidirectional"))
    )
    (net (code "141") (name "unconnected-(U$7-PadP1.5_A5)") (class "Default")
      (node (ref "U$7") (pin "P1.5_A5") (pinfunction "P1.5_A5_P1.5_A5") (pintype "bidirectional"))
    )
    (net (code "142") (name "unconnected-(U$7-PadP2.5_GPIO)") (class "Default")
      (node (ref "U$7") (pin "P2.5_GPIO") (pinfunction "P2.5_GPIO_P2.5_GPIO") (pintype "bidirectional"))
    )
    (net (code "143") (name "unconnected-(U$7-PadP2.7_SPI-CS3)") (class "Default")
      (node (ref "U$7") (pin "P2.7_SPI-CS3") (pinfunction "P2.7_SPI-CS3_P2.7_SPI-CS3") (pintype "bidirectional"))
    )
    (net (code "144") (name "unconnected-(U$7-PadP3.0_A12)") (class "Default")
      (node (ref "U$7") (pin "P3.0_A12") (pinfunction "P3.0_A12_P3.0_A12") (pintype "bidirectional"))
    )
    (net (code "145") (name "unconnected-(U$7-PadP3.1_A13)") (class "Default")
      (node (ref "U$7") (pin "P3.1_A13") (pinfunction "P3.1_A13_P3.1_A13") (pintype "bidirectional"))
    )
    (net (code "146") (name "unconnected-(U$7-PadP3.2_A14)") (class "Default")
      (node (ref "U$7") (pin "P3.2_A14") (pinfunction "P3.2_A14_P3.2_A14") (pintype "bidirectional"))
    )
    (net (code "147") (name "unconnected-(U$7-PadP3.3_A15)") (class "Default")
      (node (ref "U$7") (pin "P3.3_A15") (pinfunction "P3.3_A15_P3.3_A15") (pintype "bidirectional"))
    )
    (net (code "148") (name "unconnected-(U$7-PadP4.0_GPIO)") (class "Default")
      (node (ref "U$7") (pin "P4.0_GPIO") (pinfunction "P4.0_GPIO_P4.0_GPIO") (pintype "bidirectional"))
    )
    (net (code "149") (name "unconnected-(U$7-PadP4.1_GPIO)") (class "Default")
      (node (ref "U$7") (pin "P4.1_GPIO") (pinfunction "P4.1_GPIO_P4.1_GPIO") (pintype "bidirectional"))
    )
    (net (code "150") (name "unconnected-(U$7-PadP4.2_GPIO)") (class "Default")
      (node (ref "U$7") (pin "P4.2_GPIO") (pinfunction "P4.2_GPIO_P4.2_GPIO") (pintype "bidirectional"))
    )
    (net (code "151") (name "unconnected-(U$7-PadP4.3_GPIO)") (class "Default")
      (node (ref "U$7") (pin "P4.3_GPIO") (pinfunction "P4.3_GPIO_P4.3_GPIO") (pintype "bidirectional"))
    )
    (net (code "152") (name "unconnected-(U$7-PadP5.0_I2C-SDA-1)") (class "Default")
      (node (ref "U$7") (pin "P5.0_I2C-SDA-1") (pinfunction "P5.0_I2C-SDA-1_P5.0_I2C-SDA-1") (pintype "bidirectional"))
    )
    (net (code "153") (name "unconnected-(U$7-PadP5.1_I2C-SCL-1)") (class "Default")
      (node (ref "U$7") (pin "P5.1_I2C-SCL-1") (pinfunction "P5.1_I2C-SCL-1_P5.1_I2C-SCL-1") (pintype "bidirectional"))
    )
    (net (code "154") (name "unconnected-(U$7-PadP5.4_SPI-MOSI)") (class "Default")
      (node (ref "U$7") (pin "P5.4_SPI-MOSI") (pinfunction "P5.4_SPI-MOSI_P5.4_SPI-MOSI") (pintype "bidirectional"))
    )
    (net (code "155") (name "unconnected-(U$7-PadP5.5_SPI-MISO)") (class "Default")
      (node (ref "U$7") (pin "P5.5_SPI-MISO") (pinfunction "P5.5_SPI-MISO_P5.5_SPI-MISO") (pintype "bidirectional"))
    )
    (net (code "156") (name "unconnected-(U$7-PadP5.6_SPI-CLK)") (class "Default")
      (node (ref "U$7") (pin "P5.6_SPI-CLK") (pinfunction "P5.6_SPI-CLK_P5.6_SPI-CLK") (pintype "bidirectional"))
    )
    (net (code "157") (name "unconnected-(U$7-PadP7.0_I2C-SDA-2)") (class "Default")
      (node (ref "U$7") (pin "P7.0_I2C-SDA-2") (pinfunction "P7.0_I2C-SDA-2_P7.0_I2C-SDA-2") (pintype "bidirectional"))
    )
    (net (code "158") (name "unconnected-(U$7-PadP7.1_I2C-SCL-2)") (class "Default")
      (node (ref "U$7") (pin "P7.1_I2C-SCL-2") (pinfunction "P7.1_I2C-SCL-2_P7.1_I2C-SCL-2") (pintype "bidirectional"))
    )
    (net (code "159") (name "unconnected-(U$7-PadP7.3_GPIO)") (class "Default")
      (node (ref "U$7") (pin "P7.3_GPIO") (pinfunction "P7.3_GPIO_P7.3_GPIO") (pintype "bidirectional"))
    )
    (net (code "160") (name "unconnected-(U$7-PadP7.4_GPIO)") (class "Default")
      (node (ref "U$7") (pin "P7.4_GPIO") (pinfunction "P7.4_GPIO_P7.4_GPIO") (pintype "bidirectional"))
    )
  )
)
